# DigitalInputs.net
KiCad netlist of a schematic drawn in Altium Designer
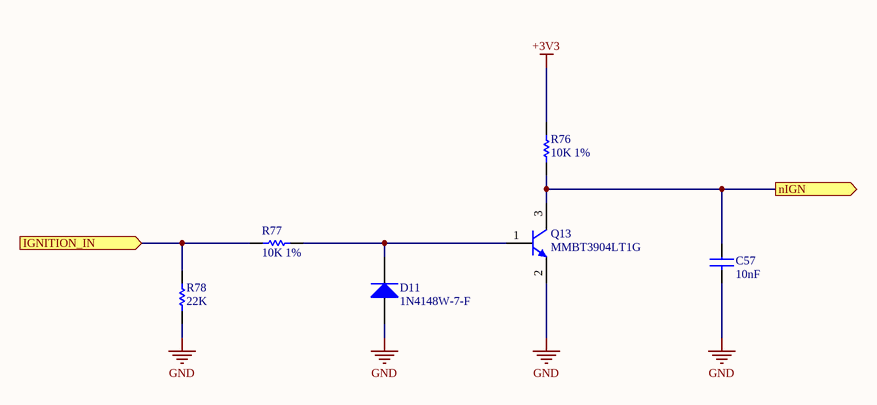
[diagram p0: DigitalInputs.SchDoc]

(export (version "E")
  (design (tool "Eeschema 10.0.6"))
  (components
    (comp (ref "C57")
      (value "10nF")
      (footprint "C0805")
      (fields
        (field (name "MANUFACTURER") "Yageo")
        (field (name "MANUFACTURER PART NUMBER") "CC0805KRX7R9BB103")
        (field (name "TOLERANCE") "10%")
      )
      (libsource (lib "MCx") (part "CC0805KRX7R9BB103"))
    )
    (comp (ref "D11")
      (value "1N4148W-7-F")
      (footprint "MC1:DIOD-SOD123-2_V")
      (description "DIODE GEN PURP 100V 300MA SOD123")
      (fields (field (name "MANUFACTURER") "Diodes") (field (name "VOLTAGE") "100V"))
      (libsource (lib "MC1") (part "1N4148W-7-F"))
    )
    (comp (ref "Q13")
      (value "MMBT3904LT1G")
      (footprint "MC1:ONSC-SOT-23-3-318-08_V")
      (description "ON Semi MMBT3904LT1G NPN Bipolar Transistor, 0.2 A, 40 V, 3-Pin SOT-23")
      (fields (field (name "MANUFACTURER") "ON Semiconductor"))
      (libsource (lib "MC1") (part "MMBT3904LT1G"))
    )
    (comp (ref "R76")
      (value "10K 1%")
      (footprint "R0805")
      (fields
        (field (name "MANUFACTURER") "Vishay")
        (field (name "MANUFACTURER PART NUMBER") "CRCW080510K0FKEA")
        (field (name "TOLERANCE") "1%")
      )
      (libsource (lib "MCx") (part "CRCW080510K0FKEA"))
    )
    (comp (ref "R77")
      (value "10K 1%")
      (footprint "R0805")
      (fields
        (field (name "MANUFACTURER") "Vishay")
        (field (name "MANUFACTURER PART NUMBER") "CRCW080510K0FKEA")
        (field (name "TOLERANCE") "1%")
      )
      (libsource (lib "MCx") (part "CRCW080510K0FKEA"))
    )
    (comp (ref "R78")
      (value "22K")
      (footprint "R0805")
      (fields
        (field (name "MANUFACTURER") "Panasonic")
        (field (name "MANUFACTURER PART NUMBER") "ERJ6ENF2202V")
        (field (name "TOLERANCE") "1%")
      )
      (libsource (lib "MCx") (part "ERJ6ENF2202V"))
    )
  )
  (nets
    (net (code "1") (name "+3V3") (class "Default")
      (node (ref "R76") (pin "2") (pinfunction "2_2") (pintype "passive"))
    )
    (net (code "2") (name "/IGNITION_IN") (class "Default")
      (node (ref "R77") (pin "1") (pinfunction "1_1") (pintype "passive"))
      (node (ref "R78") (pin "2") (pinfunction "2_2") (pintype "passive"))
    )
    (net (code "3") (name "/nIGN") (class "Default")
      (node (ref "C57") (pin "1") (pinfunction "1_1") (pintype "passive"))
      (node (ref "Q13") (pin "3") (pinfunction "C_3") (pintype "passive"))
      (node (ref "R76") (pin "1") (pinfunction "1_1") (pintype "passive"))
    )
    (net (code "4") (name "GND") (class "Default")
      (node (ref "C57") (pin "2") (pinfunction "2_2") (pintype "passive"))
      (node (ref "D11") (pin "1") (pinfunction "A_1") (pintype "passive"))
      (node (ref "Q13") (pin "2") (pinfunction "E_2") (pintype "passive"))
      (node (ref "R78") (pin "1") (pinfunction "1_1") (pintype "passive"))
    )
    (net (code "5") (name "Net-(D11-K)") (class "Default")
      (node (ref "D11") (pin "2") (pinfunction "K_2") (pintype "passive"))
      (node (ref "Q13") (pin "1") (pinfunction "B_1") (pintype "passive"))
      (node (ref "R77") (pin "2") (pinfunction "2_2") (pintype "passive"))
    )
  )
)
